# fm_trap.net
KiCad netlist of a schematic drawn in EAGLE
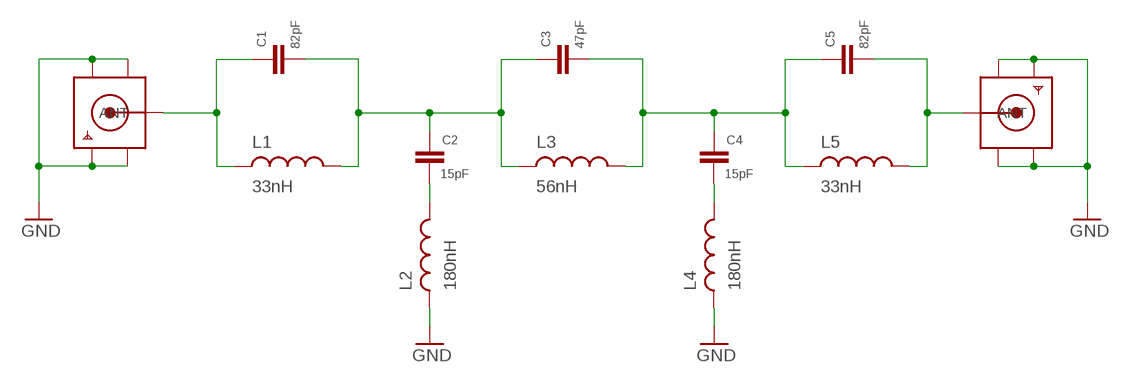
[diagram p0: schematic, sheet 1]

(export (version "E")
  (design (tool "Eeschema 10.0.6"))
  (components
    (comp (ref "C1")
      (value "82pF")
      (footprint "eagle-import:0805")
      (libsource (lib "eagle-import") (part "0805CAP"))
    )
    (comp (ref "C2")
      (value "15pF")
      (footprint "eagle-import:0805")
      (libsource (lib "eagle-import") (part "0805CAP"))
    )
    (comp (ref "C3")
      (value "47pF")
      (footprint "eagle-import:0805")
      (libsource (lib "eagle-import") (part "0805CAP"))
    )
    (comp (ref "C4")
      (value "15pF")
      (footprint "eagle-import:0805")
      (libsource (lib "eagle-import") (part "0805CAP"))
    )
    (comp (ref "C5")
      (value "82pF")
      (footprint "eagle-import:0805")
      (libsource (lib "eagle-import") (part "0805CAP"))
    )
    (comp (ref "L1")
      (value "33nH")
      (footprint "eagle-import:1008INDUCTOR")
      (libsource (lib "eagle-import") (part "1008INDUCTOR"))
    )
    (comp (ref "L2")
      (value "180nH")
      (footprint "eagle-import:1008INDUCTOR")
      (libsource (lib "eagle-import") (part "1008INDUCTOR"))
    )
    (comp (ref "L3")
      (value "56nH")
      (footprint "eagle-import:1008INDUCTOR")
      (libsource (lib "eagle-import") (part "1008INDUCTOR"))
    )
    (comp (ref "L4")
      (value "180nH")
      (footprint "eagle-import:1008INDUCTOR")
      (libsource (lib "eagle-import") (part "1008INDUCTOR"))
    )
    (comp (ref "L5")
      (value "33nH")
      (footprint "eagle-import:1008INDUCTOR")
      (libsource (lib "eagle-import") (part "1008INDUCTOR"))
    )
    (comp (ref "X1")
      (value "SMACONNECTOR_EDGE")
      (footprint "eagle-import:SMA_EDGELAUNCH")
      (libsource (lib "eagle-import") (part "SMACONNECTOR_EDGE"))
    )
    (comp (ref "X2")
      (value "SMACONNECTOR_EDGE")
      (footprint "eagle-import:SMA_EDGELAUNCH")
      (libsource (lib "eagle-import") (part "SMACONNECTOR_EDGE"))
    )
  )
  (nets
    (net (code "1") (name "GND") (class "Default")
      (node (ref "L2") (pin "P$1") (pinfunction "P$1_P$1") (pintype "bidirectional"))
      (node (ref "L4") (pin "P$1") (pinfunction "P$1_P$1") (pintype "bidirectional"))
      (node (ref "X1") (pin "GND@1") (pinfunction "GND4_GND@1") (pintype "power_in"))
      (node (ref "X1") (pin "GND@2") (pinfunction "GND3_GND@2") (pintype "power_in"))
      (node (ref "X1") (pin "GND@3") (pinfunction "GND2_GND@3") (pintype "power_in"))
      (node (ref "X1") (pin "GND@4") (pinfunction "GND1_GND@4") (pintype "power_in"))
      (node (ref "X2") (pin "GND@1") (pinfunction "GND4_GND@1") (pintype "power_in"))
      (node (ref "X2") (pin "GND@2") (pinfunction "GND3_GND@2") (pintype "power_in"))
      (node (ref "X2") (pin "GND@3") (pinfunction "GND2_GND@3") (pintype "power_in"))
      (node (ref "X2") (pin "GND@4") (pinfunction "GND1_GND@4") (pintype "power_in"))
    )
    (net (code "2") (name "Net-(C1-PadP$1)") (class "Default")
      (node (ref "C1") (pin "P$1") (pinfunction "P$1_P$1") (pintype "bidirectional"))
      (node (ref "C2") (pin "P$2") (pinfunction "P$2_P$2") (pintype "bidirectional"))
      (node (ref "C3") (pin "P$2") (pinfunction "P$2_P$2") (pintype "bidirectional"))
      (node (ref "L1") (pin "P$2") (pinfunction "P$2_P$2") (pintype "bidirectional"))
      (node (ref "L3") (pin "P$1") (pinfunction "P$1_P$1") (pintype "bidirectional"))
    )
    (net (code "3") (name "Net-(C2-PadP$1)") (class "Default")
      (node (ref "C2") (pin "P$1") (pinfunction "P$1_P$1") (pintype "bidirectional"))
      (node (ref "L2") (pin "P$2") (pinfunction "P$2_P$2") (pintype "bidirectional"))
    )
    (net (code "4") (name "Net-(C3-PadP$1)") (class "Default")
      (node (ref "C3") (pin "P$1") (pinfunction "P$1_P$1") (pintype "bidirectional"))
      (node (ref "C4") (pin "P$2") (pinfunction "P$2_P$2") (pintype "bidirectional"))
      (node (ref "C5") (pin "P$2") (pinfunction "P$2_P$2") (pintype "bidirectional"))
      (node (ref "L3") (pin "P$2") (pinfunction "P$2_P$2") (pintype "bidirectional"))
      (node (ref "L5") (pin "P$1") (pinfunction "P$1_P$1") (pintype "bidirectional"))
    )
    (net (code "5") (name "Net-(C4-PadP$1)") (class "Default")
      (node (ref "C4") (pin "P$1") (pinfunction "P$1_P$1") (pintype "bidirectional"))
      (node (ref "L4") (pin "P$2") (pinfunction "P$2_P$2") (pintype "bidirectional"))
    )
    (net (code "6") (name "Net-(X1-ANT)") (class "Default")
      (node (ref "C1") (pin "P$2") (pinfunction "P$2_P$2") (pintype "bidirectional"))
      (node (ref "L1") (pin "P$1") (pinfunction "P$1_P$1") (pintype "bidirectional"))
      (node (ref "X1") (pin "P") (pinfunction "ANT_P") (pintype "bidirectional"))
    )
    (net (code "7") (name "Net-(X2-ANT)") (class "Default")
      (node (ref "C5") (pin "P$1") (pinfunction "P$1_P$1") (pintype "bidirectional"))
      (node (ref "L5") (pin "P$2") (pinfunction "P$2_P$2") (pintype "bidirectional"))
      (node (ref "X2") (pin "P") (pinfunction "ANT_P") (pintype "bidirectional"))
    )
  )
)
